# 4017_simple_sequencer_v2.net
KiCad netlist of a schematic drawn in EasyEDA
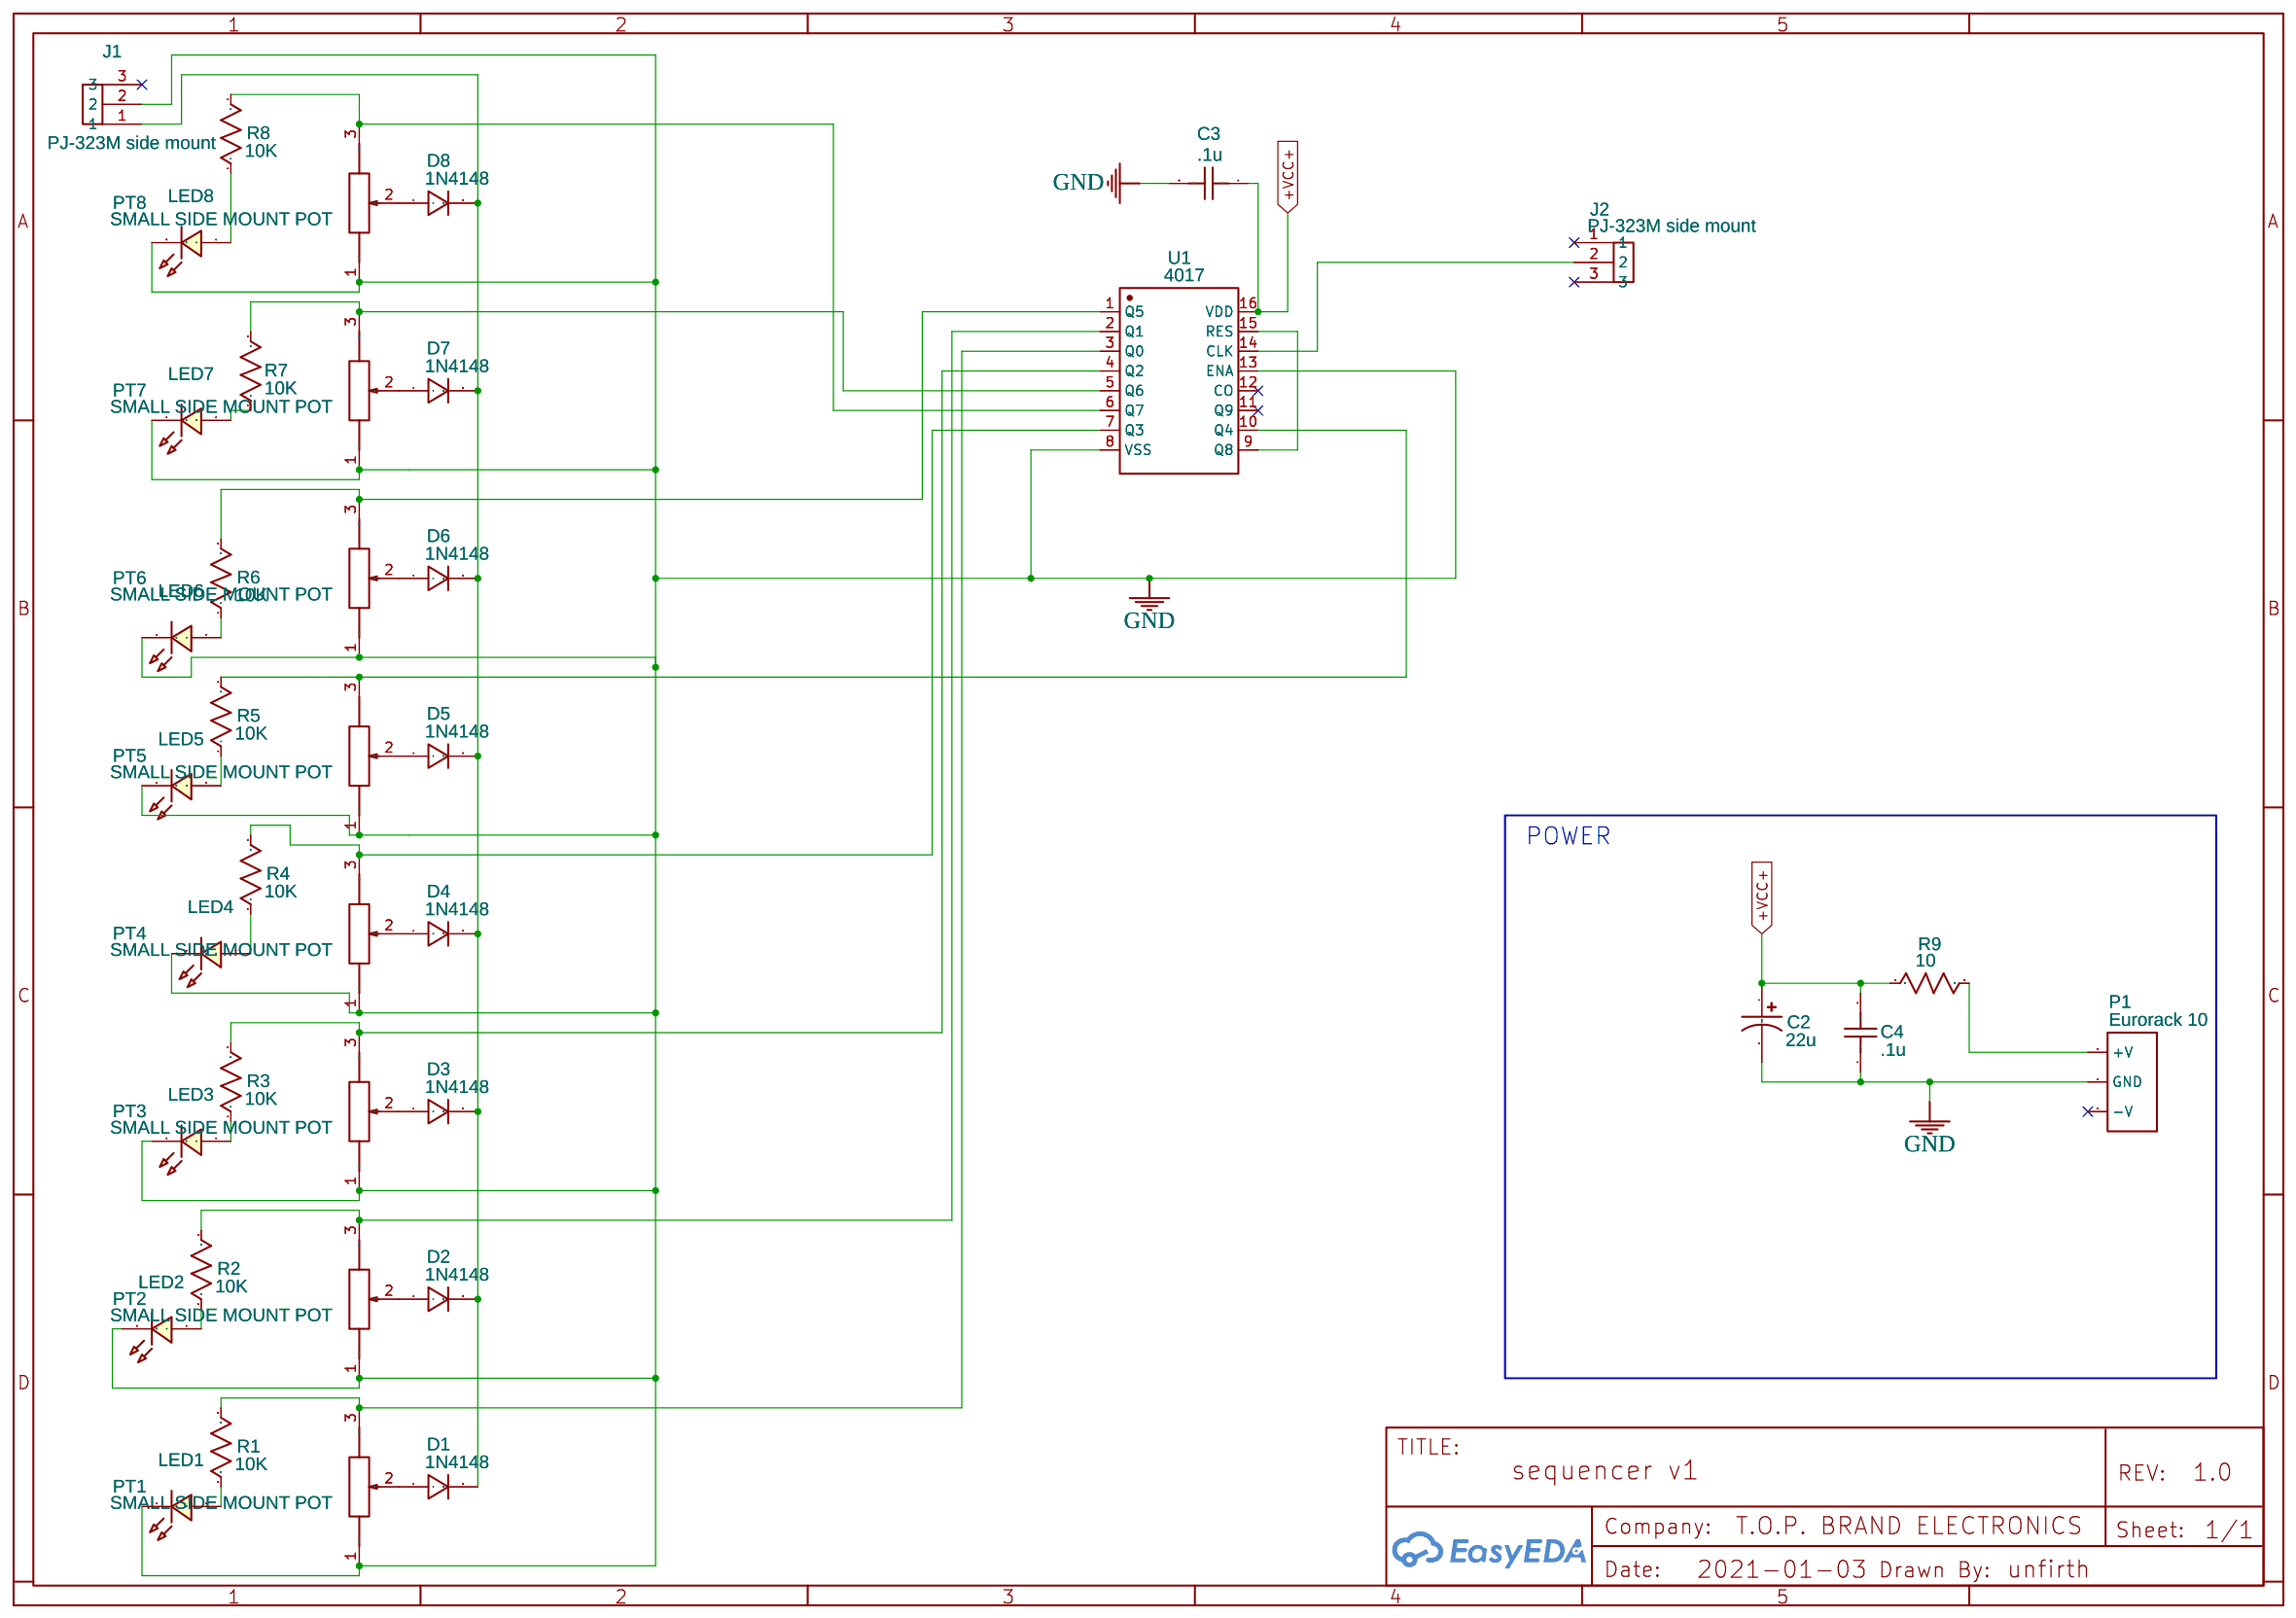
[diagram p0: schematic sheet]

(export (version "E")
  (design (tool "Eeschema 10.0.6"))
  (components
    (comp (ref "C2") (value "22u") (libsource (lib "") (part "CE_TH_D5.0×F2.0_US")))
    (comp (ref "C3") (value ".1u") (libsource (lib "") (part "C_RAD-0.1_US")))
    (comp (ref "C4") (value ".1u") (libsource (lib "") (part "C_RAD-0.1_US_1")))
    (comp (ref "D1")
      (value "1N4148")
      (fields (field (name "BOM_Supplier Part") "C14516"))
      (libsource (lib "") (part "1N4148"))
    )
    (comp (ref "D2")
      (value "1N4148")
      (fields (field (name "BOM_Supplier Part") "C14516"))
      (libsource (lib "") (part "1N4148"))
    )
    (comp (ref "D3")
      (value "1N4148")
      (fields (field (name "BOM_Supplier Part") "C14516"))
      (libsource (lib "") (part "1N4148"))
    )
    (comp (ref "D4")
      (value "1N4148")
      (fields (field (name "BOM_Supplier Part") "C14516"))
      (libsource (lib "") (part "1N4148"))
    )
    (comp (ref "D5")
      (value "1N4148")
      (fields (field (name "BOM_Supplier Part") "C14516"))
      (libsource (lib "") (part "1N4148"))
    )
    (comp (ref "D6")
      (value "1N4148")
      (fields (field (name "BOM_Supplier Part") "C14516"))
      (libsource (lib "") (part "1N4148"))
    )
    (comp (ref "D7")
      (value "1N4148")
      (fields (field (name "BOM_Supplier Part") "C14516"))
      (libsource (lib "") (part "1N4148"))
    )
    (comp (ref "D8")
      (value "1N4148")
      (fields (field (name "BOM_Supplier Part") "C14516"))
      (libsource (lib "") (part "1N4148"))
    )
    (comp (ref "J1")
      (value "PJ-323M side mount")
      (fields (field (name "BOM_Manufacturer Part") "PJ-323M"))
      (libsource (lib "") (part "PJ-323M side mount_1"))
    )
    (comp (ref "J2")
      (value "PJ-323M side mount")
      (fields (field (name "BOM_Manufacturer Part") "PJ-323M"))
      (libsource (lib "") (part "PJ-323M side mount"))
    )
    (comp (ref "LED1")
      (value "LED-TH-3mm_B")
      (fields
        (field (name "BOM_Manufacturer Part") "204-10SUBC/S400-A4")
        (field (name "BOM_Supplier Part") "C86881")
      )
      (libsource (lib "") (part "LED-TH-3mm_B"))
    )
    (comp (ref "LED2")
      (value "LED-TH-3mm_B")
      (fields
        (field (name "BOM_Manufacturer Part") "204-10SUBC/S400-A4")
        (field (name "BOM_Supplier Part") "C86881")
      )
      (libsource (lib "") (part "LED-TH-3mm_B"))
    )
    (comp (ref "LED3")
      (value "LED-TH-3mm_B")
      (fields
        (field (name "BOM_Manufacturer Part") "204-10SUBC/S400-A4")
        (field (name "BOM_Supplier Part") "C86881")
      )
      (libsource (lib "") (part "LED-TH-3mm_B"))
    )
    (comp (ref "LED4")
      (value "LED-TH-3mm_B")
      (fields
        (field (name "BOM_Manufacturer Part") "204-10SUBC/S400-A4")
        (field (name "BOM_Supplier Part") "C86881")
      )
      (libsource (lib "") (part "LED-TH-3mm_B"))
    )
    (comp (ref "LED5")
      (value "LED-TH-3mm_B")
      (fields
        (field (name "BOM_Manufacturer Part") "204-10SUBC/S400-A4")
        (field (name "BOM_Supplier Part") "C86881")
      )
      (libsource (lib "") (part "LED-TH-3mm_B"))
    )
    (comp (ref "LED6")
      (value "LED-TH-3mm_B")
      (fields
        (field (name "BOM_Manufacturer Part") "204-10SUBC/S400-A4")
        (field (name "BOM_Supplier Part") "C86881")
      )
      (libsource (lib "") (part "LED-TH-3mm_B"))
    )
    (comp (ref "LED7")
      (value "LED-TH-3mm_B")
      (fields
        (field (name "BOM_Manufacturer Part") "204-10SUBC/S400-A4")
        (field (name "BOM_Supplier Part") "C86881")
      )
      (libsource (lib "") (part "LED-TH-3mm_B"))
    )
    (comp (ref "LED8")
      (value "LED-TH-3mm_B")
      (fields
        (field (name "BOM_Manufacturer Part") "204-10SUBC/S400-A4")
        (field (name "BOM_Supplier Part") "C86881")
      )
      (libsource (lib "") (part "LED-TH-3mm_B"))
    )
    (comp (ref "P1")
      (value "Eurorack 10")
      (fields
        (field (name "BOM_Manufacturer Part") "IDC Box 2.54mm 2X5P")
        (field (name "BOM_Supplier Part") "C5665")
      )
      (libsource (lib "") (part "Eurorack 2x5p 2.54mm"))
    )
    (comp (ref "PT1") (value "SMALL SIDE MOUNT POT") (libsource (lib "") (part "SMALL SIDE MOUNT POT")))
    (comp (ref "PT2") (value "SMALL SIDE MOUNT POT") (libsource (lib "") (part "SMALL SIDE MOUNT POT")))
    (comp (ref "PT3") (value "SMALL SIDE MOUNT POT") (libsource (lib "") (part "SMALL SIDE MOUNT POT")))
    (comp (ref "PT4") (value "SMALL SIDE MOUNT POT") (libsource (lib "") (part "SMALL SIDE MOUNT POT")))
    (comp (ref "PT5") (value "SMALL SIDE MOUNT POT") (libsource (lib "") (part "SMALL SIDE MOUNT POT")))
    (comp (ref "PT6") (value "SMALL SIDE MOUNT POT") (libsource (lib "") (part "SMALL SIDE MOUNT POT")))
    (comp (ref "PT7") (value "SMALL SIDE MOUNT POT") (libsource (lib "") (part "SMALL SIDE MOUNT POT")))
    (comp (ref "PT8") (value "SMALL SIDE MOUNT POT") (libsource (lib "") (part "SMALL SIDE MOUNT POT")))
    (comp (ref "R1") (value "10K") (libsource (lib "") (part "R_AXIAL-0.5_US")))
    (comp (ref "R2") (value "10K") (libsource (lib "") (part "R_AXIAL-0.5_US")))
    (comp (ref "R3") (value "10K") (libsource (lib "") (part "R_AXIAL-0.5_US")))
    (comp (ref "R4") (value "10K") (libsource (lib "") (part "R_AXIAL-0.5_US")))
    (comp (ref "R5") (value "10K") (libsource (lib "") (part "R_AXIAL-0.5_US")))
    (comp (ref "R6") (value "10K") (libsource (lib "") (part "R_AXIAL-0.5_US")))
    (comp (ref "R7") (value "10K") (libsource (lib "") (part "R_AXIAL-0.5_US")))
    (comp (ref "R8") (value "10K") (libsource (lib "") (part "R_AXIAL-0.5_US")))
    (comp (ref "R9") (value "10") (libsource (lib "") (part "R_AXIAL-0.5_US_1")))
    (comp (ref "U1") (value "4017") (libsource (lib "") (part "4017")))
  )
  (nets
    (net (code "1") (name "+VCC+") (class "Default")
      (node (ref "C2") (pin "1") (pinfunction "1_1") (pintype "unspecified"))
      (node (ref "C3") (pin "1") (pinfunction "1_1") (pintype "unspecified"))
      (node (ref "C4") (pin "2") (pinfunction "2_2") (pintype "unspecified"))
      (node (ref "R9") (pin "1") (pinfunction "1_1") (pintype "unspecified"))
      (node (ref "U1") (pin "16") (pinfunction "VDD_16") (pintype "unspecified"))
    )
    (net (code "2") (name "GND") (class "Default")
      (node (ref "C2") (pin "2") (pinfunction "2_2") (pintype "unspecified"))
      (node (ref "C3") (pin "2") (pinfunction "2_2") (pintype "unspecified"))
      (node (ref "C4") (pin "1") (pinfunction "1_1") (pintype "unspecified"))
      (node (ref "J1") (pin "2") (pinfunction "2_2") (pintype "unspecified"))
      (node (ref "LED1") (pin "2") (pinfunction "2_2") (pintype "unspecified"))
      (node (ref "LED2") (pin "2") (pinfunction "2_2") (pintype "unspecified"))
      (node (ref "LED3") (pin "2") (pinfunction "2_2") (pintype "unspecified"))
      (node (ref "LED4") (pin "2") (pinfunction "2_2") (pintype "unspecified"))
      (node (ref "LED5") (pin "2") (pinfunction "2_2") (pintype "unspecified"))
      (node (ref "LED6") (pin "2") (pinfunction "2_2") (pintype "unspecified"))
      (node (ref "LED7") (pin "2") (pinfunction "2_2") (pintype "unspecified"))
      (node (ref "LED8") (pin "2") (pinfunction "2_2") (pintype "unspecified"))
      (node (ref "P1") (pin "2") (pinfunction "GND_2") (pintype "unspecified"))
      (node (ref "PT1") (pin "1") (pinfunction "1_1") (pintype "unspecified"))
      (node (ref "PT2") (pin "1") (pinfunction "1_1") (pintype "unspecified"))
      (node (ref "PT3") (pin "1") (pinfunction "1_1") (pintype "unspecified"))
      (node (ref "PT4") (pin "1") (pinfunction "1_1") (pintype "unspecified"))
      (node (ref "PT5") (pin "1") (pinfunction "1_1") (pintype "unspecified"))
      (node (ref "PT6") (pin "1") (pinfunction "1_1") (pintype "unspecified"))
      (node (ref "PT7") (pin "1") (pinfunction "1_1") (pintype "unspecified"))
      (node (ref "PT8") (pin "1") (pinfunction "1_1") (pintype "unspecified"))
      (node (ref "U1") (pin "13") (pinfunction "ENA_13") (pintype "unspecified"))
      (node (ref "U1") (pin "8") (pinfunction "VSS_8") (pintype "unspecified"))
    )
    (net (code "3") (name "Net-(D1-Pad1)") (class "Default")
      (node (ref "D1") (pin "1") (pinfunction "1_1") (pintype "unspecified"))
      (node (ref "PT1") (pin "2") (pinfunction "2_2") (pintype "unspecified"))
    )
    (net (code "4") (name "Net-(D1-Pad2)") (class "Default")
      (node (ref "D1") (pin "2") (pinfunction "2_2") (pintype "unspecified"))
      (node (ref "D2") (pin "2") (pinfunction "2_2") (pintype "unspecified"))
      (node (ref "D3") (pin "2") (pinfunction "2_2") (pintype "unspecified"))
      (node (ref "D4") (pin "2") (pinfunction "2_2") (pintype "unspecified"))
      (node (ref "D5") (pin "2") (pinfunction "2_2") (pintype "unspecified"))
      (node (ref "D6") (pin "2") (pinfunction "2_2") (pintype "unspecified"))
      (node (ref "D7") (pin "2") (pinfunction "2_2") (pintype "unspecified"))
      (node (ref "D8") (pin "2") (pinfunction "2_2") (pintype "unspecified"))
      (node (ref "J1") (pin "1") (pinfunction "1_1") (pintype "unspecified"))
    )
    (net (code "5") (name "Net-(D2-Pad1)") (class "Default")
      (node (ref "D2") (pin "1") (pinfunction "1_1") (pintype "unspecified"))
      (node (ref "PT2") (pin "2") (pinfunction "2_2") (pintype "unspecified"))
    )
    (net (code "6") (name "Net-(D3-Pad1)") (class "Default")
      (node (ref "D3") (pin "1") (pinfunction "1_1") (pintype "unspecified"))
      (node (ref "PT3") (pin "2") (pinfunction "2_2") (pintype "unspecified"))
    )
    (net (code "7") (name "Net-(D4-Pad1)") (class "Default")
      (node (ref "D4") (pin "1") (pinfunction "1_1") (pintype "unspecified"))
      (node (ref "PT4") (pin "2") (pinfunction "2_2") (pintype "unspecified"))
    )
    (net (code "8") (name "Net-(D5-Pad1)") (class "Default")
      (node (ref "D5") (pin "1") (pinfunction "1_1") (pintype "unspecified"))
      (node (ref "PT5") (pin "2") (pinfunction "2_2") (pintype "unspecified"))
    )
    (net (code "9") (name "Net-(D6-Pad1)") (class "Default")
      (node (ref "D6") (pin "1") (pinfunction "1_1") (pintype "unspecified"))
      (node (ref "PT6") (pin "2") (pinfunction "2_2") (pintype "unspecified"))
    )
    (net (code "10") (name "Net-(D7-Pad1)") (class "Default")
      (node (ref "D7") (pin "1") (pinfunction "1_1") (pintype "unspecified"))
      (node (ref "PT7") (pin "2") (pinfunction "2_2") (pintype "unspecified"))
    )
    (net (code "11") (name "Net-(D8-Pad1)") (class "Default")
      (node (ref "D8") (pin "1") (pinfunction "1_1") (pintype "unspecified"))
      (node (ref "PT8") (pin "2") (pinfunction "2_2") (pintype "unspecified"))
    )
    (net (code "12") (name "Net-(LED1-Pad1)") (class "Default")
      (node (ref "LED1") (pin "1") (pinfunction "1_1") (pintype "unspecified"))
      (node (ref "R1") (pin "1") (pinfunction "1_1") (pintype "unspecified"))
    )
    (net (code "13") (name "Net-(LED2-Pad1)") (class "Default")
      (node (ref "LED2") (pin "1") (pinfunction "1_1") (pintype "unspecified"))
      (node (ref "R2") (pin "1") (pinfunction "1_1") (pintype "unspecified"))
    )
    (net (code "14") (name "Net-(LED3-Pad1)") (class "Default")
      (node (ref "LED3") (pin "1") (pinfunction "1_1") (pintype "unspecified"))
      (node (ref "R3") (pin "1") (pinfunction "1_1") (pintype "unspecified"))
    )
    (net (code "15") (name "Net-(LED4-Pad1)") (class "Default")
      (node (ref "LED4") (pin "1") (pinfunction "1_1") (pintype "unspecified"))
      (node (ref "R4") (pin "1") (pinfunction "1_1") (pintype "unspecified"))
    )
    (net (code "16") (name "Net-(LED5-Pad1)") (class "Default")
      (node (ref "LED5") (pin "1") (pinfunction "1_1") (pintype "unspecified"))
      (node (ref "R5") (pin "1") (pinfunction "1_1") (pintype "unspecified"))
    )
    (net (code "17") (name "Net-(LED6-Pad1)") (class "Default")
      (node (ref "LED6") (pin "1") (pinfunction "1_1") (pintype "unspecified"))
      (node (ref "R6") (pin "1") (pinfunction "1_1") (pintype "unspecified"))
    )
    (net (code "18") (name "Net-(LED7-Pad1)") (class "Default")
      (node (ref "LED7") (pin "1") (pinfunction "1_1") (pintype "unspecified"))
      (node (ref "R7") (pin "1") (pinfunction "1_1") (pintype "unspecified"))
    )
    (net (code "19") (name "Net-(LED8-Pad1)") (class "Default")
      (node (ref "LED8") (pin "1") (pinfunction "1_1") (pintype "unspecified"))
      (node (ref "R8") (pin "1") (pinfunction "1_1") (pintype "unspecified"))
    )
    (net (code "20") (name "Net-(P1-+V)") (class "Default")
      (node (ref "P1") (pin "3") (pinfunction "+V_3") (pintype "unspecified"))
      (node (ref "R9") (pin "2") (pinfunction "2_2") (pintype "unspecified"))
    )
    (net (code "21") (name "Net-(U1-CLK)") (class "Default")
      (node (ref "J2") (pin "2") (pinfunction "2_2") (pintype "unspecified"))
      (node (ref "U1") (pin "14") (pinfunction "CLK_14") (pintype "unspecified"))
    )
    (net (code "22") (name "Net-(U1-Q0)") (class "Default")
      (node (ref "PT1") (pin "3") (pinfunction "3_3") (pintype "unspecified"))
      (node (ref "R1") (pin "2") (pinfunction "2_2") (pintype "unspecified"))
      (node (ref "U1") (pin "3") (pinfunction "Q0_3") (pintype "unspecified"))
    )
    (net (code "23") (name "Net-(U1-Q1)") (class "Default")
      (node (ref "PT2") (pin "3") (pinfunction "3_3") (pintype "unspecified"))
      (node (ref "R2") (pin "2") (pinfunction "2_2") (pintype "unspecified"))
      (node (ref "U1") (pin "2") (pinfunction "Q1_2") (pintype "unspecified"))
    )
    (net (code "24") (name "Net-(U1-Q2)") (class "Default")
      (node (ref "PT3") (pin "3") (pinfunction "3_3") (pintype "unspecified"))
      (node (ref "R3") (pin "2") (pinfunction "2_2") (pintype "unspecified"))
      (node (ref "U1") (pin "4") (pinfunction "Q2_4") (pintype "unspecified"))
    )
    (net (code "25") (name "Net-(U1-Q3)") (class "Default")
      (node (ref "PT4") (pin "3") (pinfunction "3_3") (pintype "unspecified"))
      (node (ref "R4") (pin "2") (pinfunction "2_2") (pintype "unspecified"))
      (node (ref "U1") (pin "7") (pinfunction "Q3_7") (pintype "unspecified"))
    )
    (net (code "26") (name "Net-(U1-Q4)") (class "Default")
      (node (ref "PT5") (pin "3") (pinfunction "3_3") (pintype "unspecified"))
      (node (ref "R5") (pin "2") (pinfunction "2_2") (pintype "unspecified"))
      (node (ref "U1") (pin "10") (pinfunction "Q4_10") (pintype "unspecified"))
    )
    (net (code "27") (name "Net-(U1-Q5)") (class "Default")
      (node (ref "PT6") (pin "3") (pinfunction "3_3") (pintype "unspecified"))
      (node (ref "R6") (pin "2") (pinfunction "2_2") (pintype "unspecified"))
      (node (ref "U1") (pin "1") (pinfunction "Q5_1") (pintype "unspecified"))
    )
    (net (code "28") (name "Net-(U1-Q6)") (class "Default")
      (node (ref "PT7") (pin "3") (pinfunction "3_3") (pintype "unspecified"))
      (node (ref "R7") (pin "2") (pinfunction "2_2") (pintype "unspecified"))
      (node (ref "U1") (pin "5") (pinfunction "Q6_5") (pintype "unspecified"))
    )
    (net (code "29") (name "Net-(U1-Q7)") (class "Default")
      (node (ref "PT8") (pin "3") (pinfunction "3_3") (pintype "unspecified"))
      (node (ref "R8") (pin "2") (pinfunction "2_2") (pintype "unspecified"))
      (node (ref "U1") (pin "6") (pinfunction "Q7_6") (pintype "unspecified"))
    )
    (net (code "30") (name "Net-(U1-Q8)") (class "Default")
      (node (ref "U1") (pin "15") (pinfunction "RES_15") (pintype "unspecified"))
      (node (ref "U1") (pin "9") (pinfunction "Q8_9") (pintype "unspecified"))
    )
    (net (code "31") (name "unconnected-(J1-Pad3)") (class "Default")
      (node (ref "J1") (pin "3") (pinfunction "3_3") (pintype "unspecified+no_connect"))
    )
    (net (code "32") (name "unconnected-(J2-Pad1)") (class "Default")
      (node (ref "J2") (pin "1") (pinfunction "1_1") (pintype "unspecified+no_connect"))
    )
    (net (code "33") (name "unconnected-(J2-Pad3)") (class "Default")
      (node (ref "J2") (pin "3") (pinfunction "3_3") (pintype "unspecified+no_connect"))
    )
    (net (code "34") (name "unconnected-(P1--V-Pad1)") (class "Default")
      (node (ref "P1") (pin "1") (pinfunction "-V_1") (pintype "unspecified+no_connect"))
    )
    (net (code "35") (name "unconnected-(U1-CO-Pad12)") (class "Default")
      (node (ref "U1") (pin "12") (pinfunction "CO_12") (pintype "unspecified+no_connect"))
    )
    (net (code "36") (name "unconnected-(U1-Q9-Pad11)") (class "Default")
      (node (ref "U1") (pin "11") (pinfunction "Q9_11") (pintype "unspecified+no_connect"))
    )
  )
)
